# SKAARDUINO-POE_v1_0.net
KiCad netlist of a schematic drawn in EAGLE
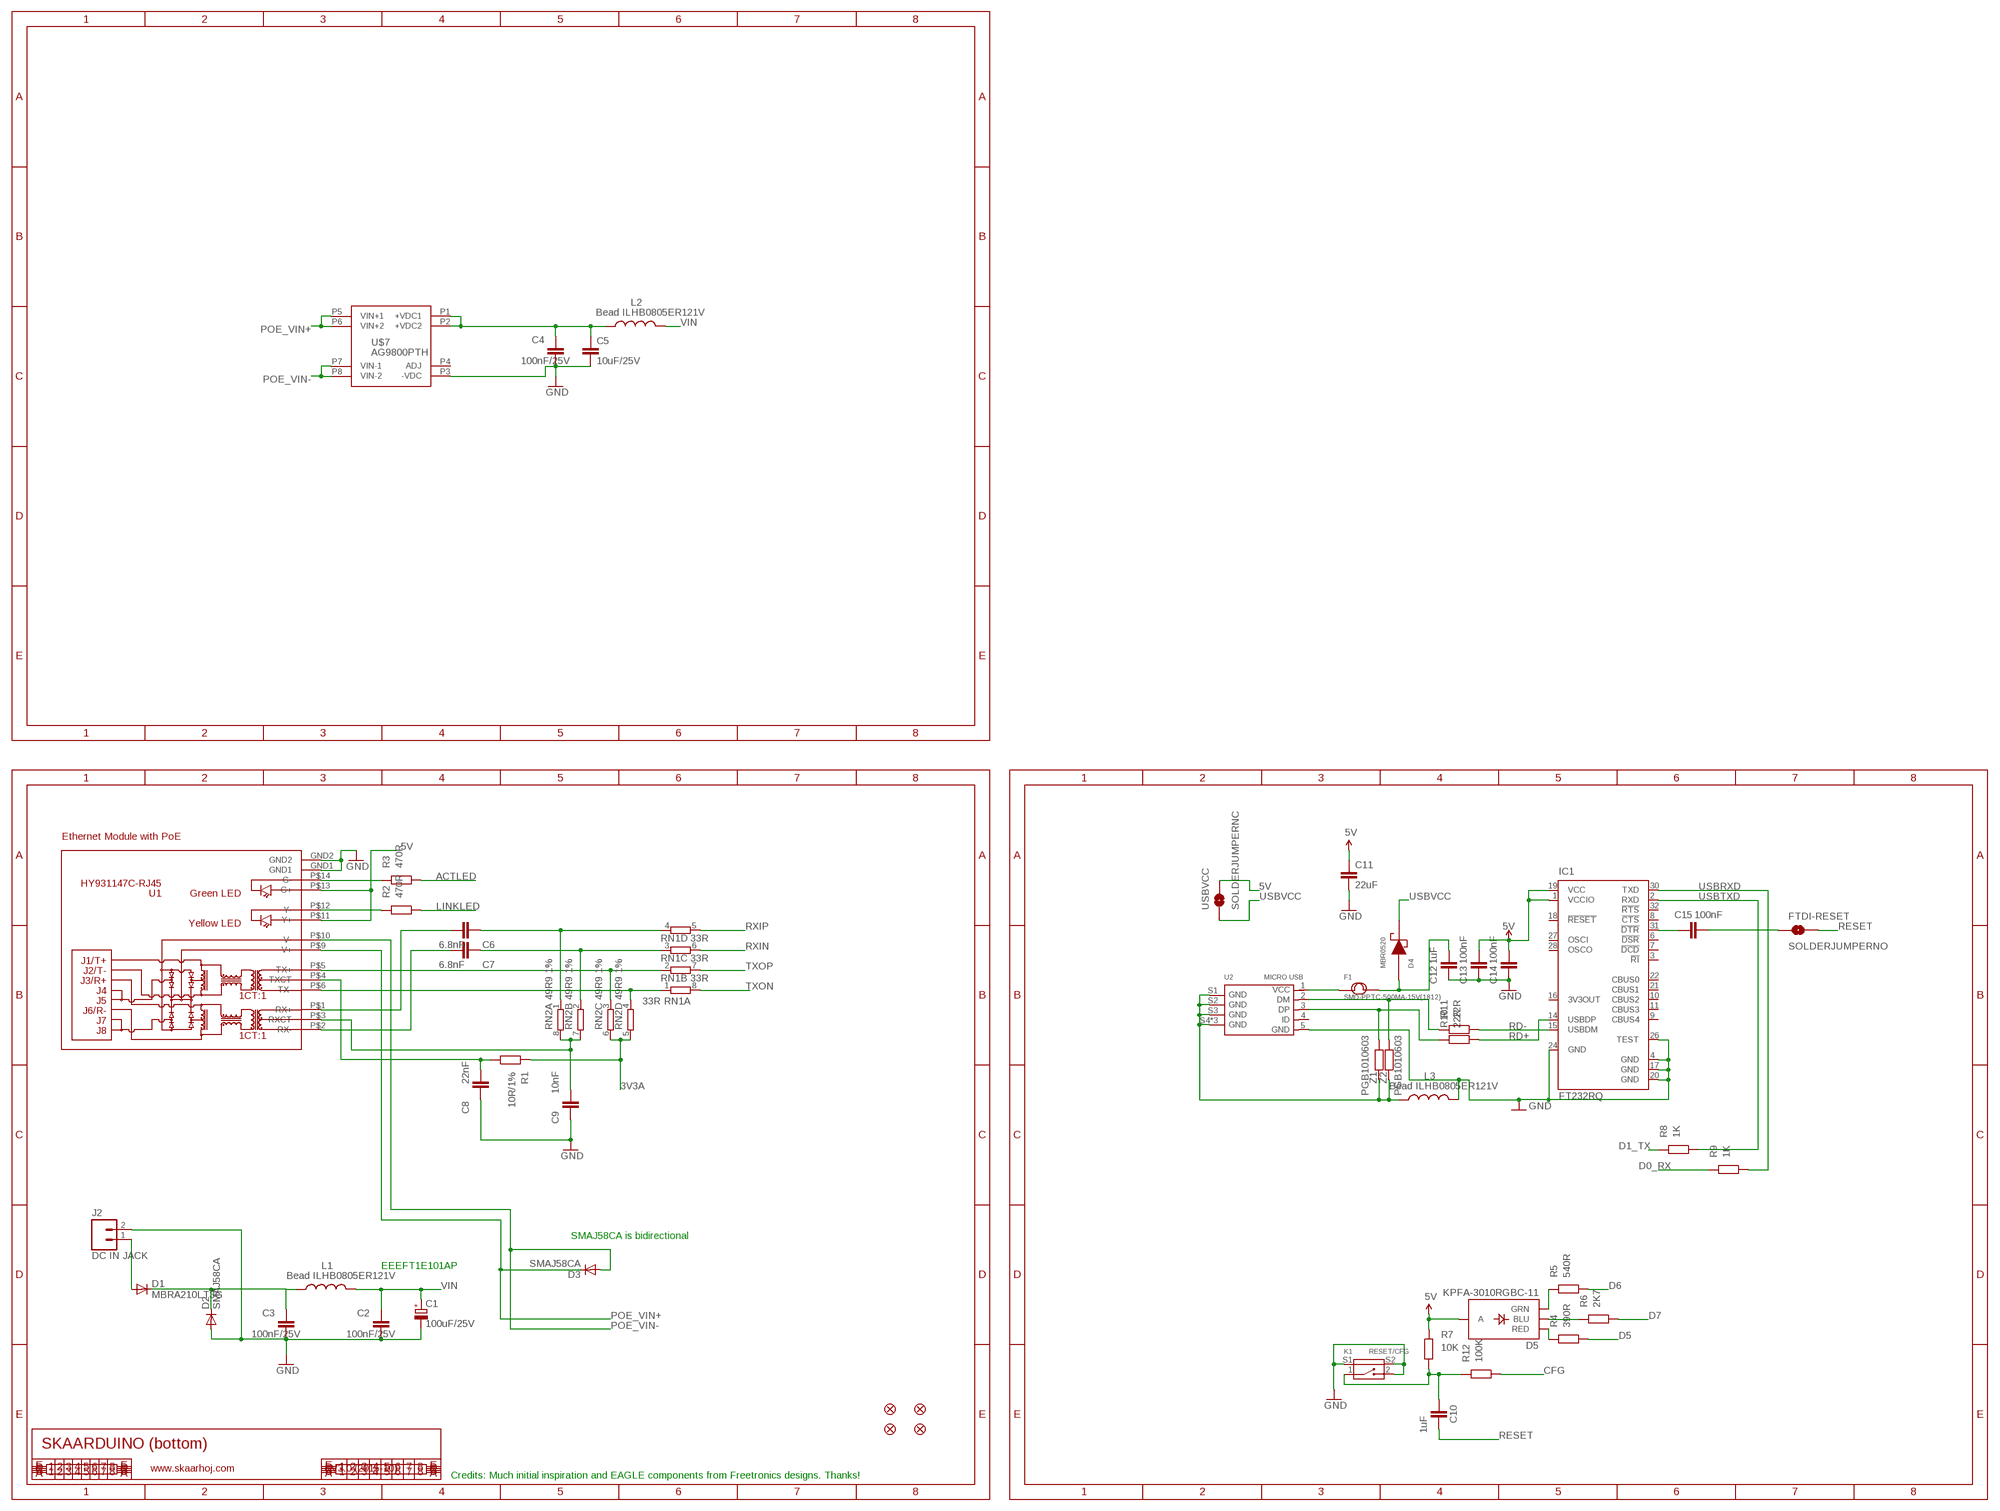
[diagram p0: schematic, sheet 1]
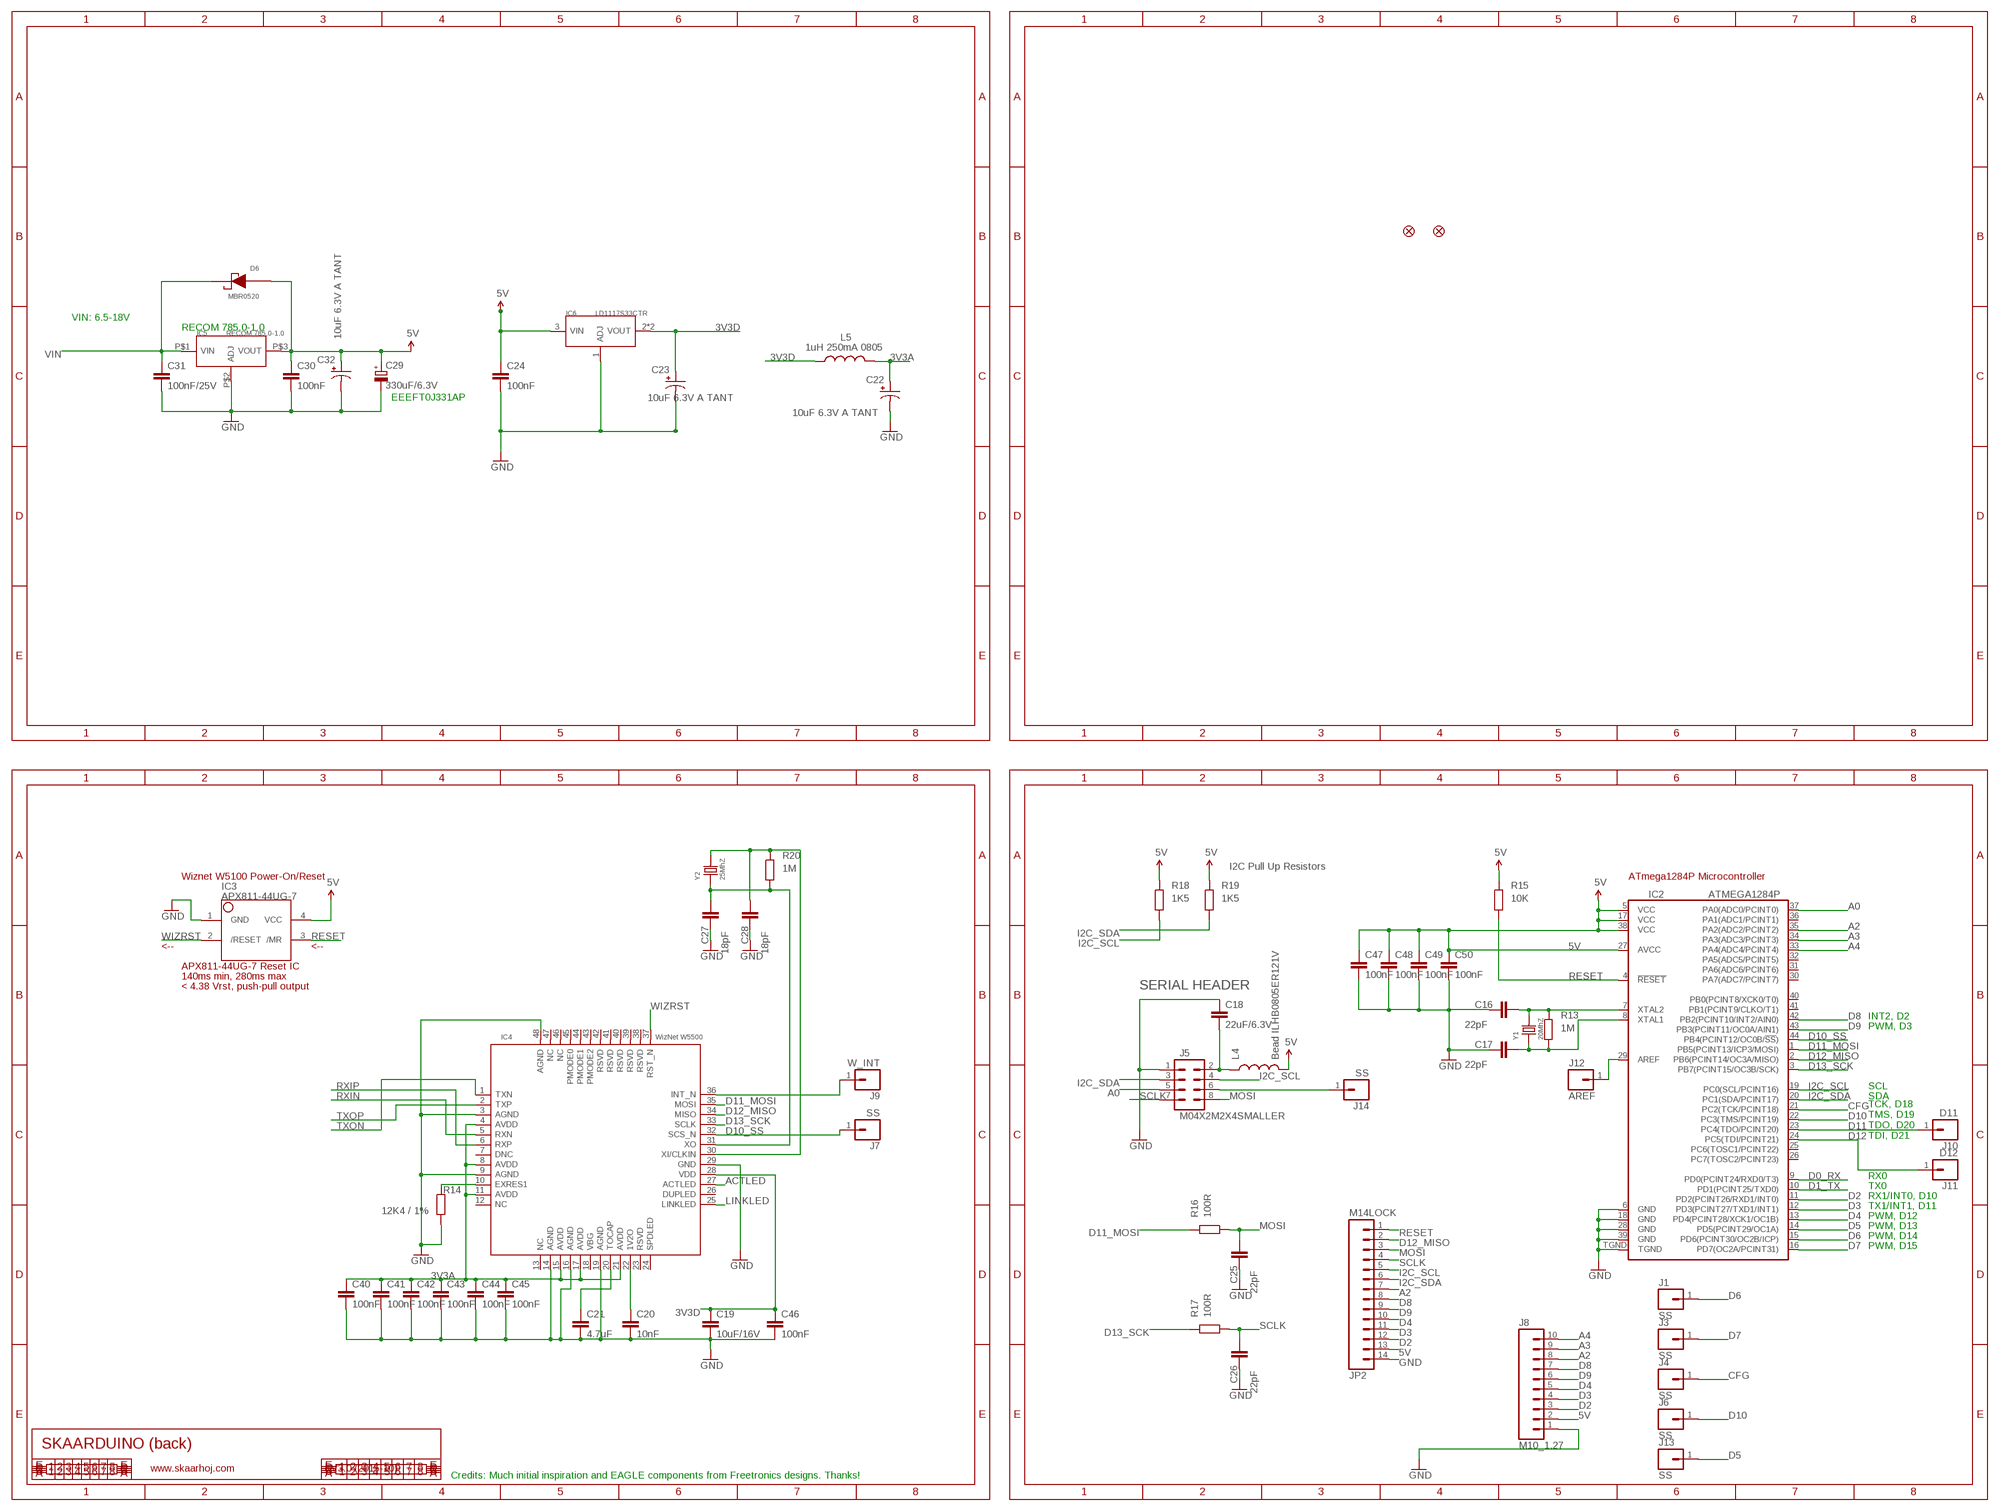
[diagram p1: schematic, sheet 2]

(export (version "E")
  (design (tool "Eeschema 10.0.6"))
  (components
    (comp (ref "C1")
      (value "100uF/25V")
      (footprint "eagle-import:PANASONIC_D")
      (libsource (lib "eagle-import") (part "CPOL-EUD"))
    )
    (comp (ref "C2")
      (value "100nF/25V")
      (footprint "eagle-import:C0402")
      (libsource (lib "eagle-import") (part "CAP0402"))
    )
    (comp (ref "C3")
      (value "100nF/25V")
      (footprint "eagle-import:C0402")
      (libsource (lib "eagle-import") (part "CAP0402"))
    )
    (comp (ref "C4")
      (value "100nF/25V")
      (footprint "eagle-import:C0402")
      (libsource (lib "eagle-import") (part "CAP0402"))
    )
    (comp (ref "C5")
      (value "10uF/25V")
      (footprint "eagle-import:0805")
      (libsource (lib "eagle-import") (part "CAP0805"))
    )
    (comp (ref "C6")
      (value "6.8nF")
      (footprint "eagle-import:0402C")
      (libsource (lib "eagle-import") (part "C-EU0402C"))
    )
    (comp (ref "C7")
      (value "6.8nF")
      (footprint "eagle-import:0402C")
      (libsource (lib "eagle-import") (part "C-EU0402C"))
    )
    (comp (ref "C8")
      (value "22nF")
      (footprint "eagle-import:0402C")
      (libsource (lib "eagle-import") (part "C-EU0402C"))
    )
    (comp (ref "C9")
      (value "10nF")
      (footprint "eagle-import:0402C")
      (libsource (lib "eagle-import") (part "C-EU0402C"))
    )
    (comp (ref "C10")
      (value "1uF")
      (footprint "eagle-import:0402C")
      (libsource (lib "eagle-import") (part "C-EU0402C"))
    )
    (comp (ref "C11")
      (value "22uF")
      (footprint "eagle-import:0805")
      (libsource (lib "eagle-import") (part "CAP0805"))
    )
    (comp (ref "C12")
      (value "1uF")
      (footprint "eagle-import:0402C")
      (libsource (lib "eagle-import") (part "C-EU0402C"))
    )
    (comp (ref "C13")
      (value "100nF")
      (footprint "eagle-import:0402C")
      (libsource (lib "eagle-import") (part "C-EU0402C"))
    )
    (comp (ref "C14")
      (value "100nF")
      (footprint "eagle-import:0402C")
      (libsource (lib "eagle-import") (part "C-EU0402C"))
    )
    (comp (ref "C15")
      (value "100nF")
      (footprint "eagle-import:0402C")
      (libsource (lib "eagle-import") (part "C-EU0402C"))
    )
    (comp (ref "D1")
      (value "MBRA210LT3G")
      (footprint "eagle-import:SMA-DIODE")
      (libsource (lib "eagle-import") (part "DIODESMA"))
    )
    (comp (ref "D2")
      (value "SMAJ58CA")
      (footprint "eagle-import:SMA-DIODE")
      (libsource (lib "eagle-import") (part "DIODESMA"))
    )
    (comp (ref "D3")
      (value "SMAJ58CA")
      (footprint "eagle-import:SMA-DIODE")
      (libsource (lib "eagle-import") (part "DIODESMA"))
    )
    (comp (ref "D4")
      (value "MBR0520")
      (footprint "eagle-import:SOD-123")
      (libsource (lib "eagle-import") (part "MBR0520"))
    )
    (comp (ref "D5")
      (value "KPFA-3010RGBC-11")
      (footprint "eagle-import:LED-TRICOLOR-SMD")
      (libsource (lib "eagle-import") (part "LED-TRICOLOR"))
    )
    (comp (ref "F1")
      (value "SMD-PPTC-500MA-15V(1812)")
      (footprint "eagle-import:F1812")
      (libsource (lib "eagle-import") (part "SMD-PPTC-500MA-15V(1812)"))
    )
    (comp (ref "FID1")
      (value "FIDUCIAL1X2.5")
      (footprint "eagle-import:FIDUCIAL-1X2.5")
      (libsource (lib "eagle-import") (part "FIDUCIAL1X2.5"))
    )
    (comp (ref "FID2")
      (value "FIDUCIAL1X2.5")
      (footprint "eagle-import:FIDUCIAL-1X2.5")
      (libsource (lib "eagle-import") (part "FIDUCIAL1X2.5"))
    )
    (comp (ref "FID3")
      (value "FIDUCIAL1X2.5")
      (footprint "eagle-import:FIDUCIAL-1X2.5")
      (libsource (lib "eagle-import") (part "FIDUCIAL1X2.5"))
    )
    (comp (ref "FID4")
      (value "FIDUCIAL1X2.5")
      (footprint "eagle-import:FIDUCIAL-1X2.5")
      (libsource (lib "eagle-import") (part "FIDUCIAL1X2.5"))
    )
    (comp (ref "FTDI-RESET")
      (value "SOLDERJUMPERNO")
      (footprint "eagle-import:SJ_2S-NO")
      (libsource (lib "eagle-import") (part "SOLDERJUMPERNO"))
    )
    (comp (ref "IC1")
      (value "FT232RQ")
      (footprint "eagle-import:QFN32")
      (libsource (lib "eagle-import") (part "FT232RQ"))
    )
    (comp (ref "J2")
      (value "DC IN JACK")
      (footprint "eagle-import:1X02")
      (libsource (lib "eagle-import") (part "M02PTH"))
    )
    (comp (ref "K1")
      (value "RESET/CFG")
      (footprint "eagle-import:SW4-SMD-7.0X3.5X3.5MM-90D")
      (fields (field (name "MPN") "TS-1188E"))
      (libsource (lib "eagle-import") (part "SMD-BUTTON-2+2P"))
    )
    (comp (ref "L1")
      (value "Bead ILHB0805ER121V")
      (footprint "eagle-import:L2012C")
      (libsource (lib "eagle-import") (part "L-USL2012C"))
    )
    (comp (ref "L2")
      (value "Bead ILHB0805ER121V")
      (footprint "eagle-import:L2012C")
      (libsource (lib "eagle-import") (part "L-USL2012C"))
    )
    (comp (ref "L3")
      (value "Bead ILHB0805ER121V")
      (footprint "eagle-import:L2012C")
      (libsource (lib "eagle-import") (part "L-USL2012C"))
    )
    (comp (ref "R1")
      (value "10R/1%")
      (footprint "eagle-import:0402")
      (libsource (lib "eagle-import") (part "freetronics-jon_RESISTOR0402"))
    )
    (comp (ref "R2")
      (value "470R")
      (footprint "eagle-import:0402")
      (libsource (lib "eagle-import") (part "freetronics-jon_RESISTOR0402"))
    )
    (comp (ref "R3")
      (value "470R")
      (footprint "eagle-import:0402")
      (libsource (lib "eagle-import") (part "freetronics-jon_RESISTOR0402"))
    )
    (comp (ref "R4")
      (value "390R")
      (footprint "eagle-import:0402")
      (libsource (lib "eagle-import") (part "freetronics-jon_RESISTOR0402"))
    )
    (comp (ref "R5")
      (value "540R")
      (footprint "eagle-import:0402")
      (libsource (lib "eagle-import") (part "freetronics-jon_RESISTOR0402"))
    )
    (comp (ref "R6")
      (value "2K7")
      (footprint "eagle-import:0402")
      (libsource (lib "eagle-import") (part "freetronics-jon_RESISTOR0402"))
    )
    (comp (ref "R7")
      (value "10K")
      (footprint "eagle-import:0402")
      (libsource (lib "eagle-import") (part "freetronics-jon_RESISTOR0402"))
    )
    (comp (ref "R8")
      (value "1K")
      (footprint "eagle-import:0402")
      (libsource (lib "eagle-import") (part "freetronics-jon_RESISTOR0402"))
    )
    (comp (ref "R9")
      (value "1K")
      (footprint "eagle-import:0402")
      (libsource (lib "eagle-import") (part "freetronics-jon_RESISTOR0402"))
    )
    (comp (ref "R10")
      (value "22R")
      (footprint "eagle-import:0402")
      (libsource (lib "eagle-import") (part "freetronics-jon_RESISTOR0402"))
    )
    (comp (ref "R11")
      (value "22R")
      (footprint "eagle-import:0402")
      (libsource (lib "eagle-import") (part "freetronics-jon_RESISTOR0402"))
    )
    (comp (ref "R12")
      (value "100K")
      (footprint "eagle-import:0402")
      (libsource (lib "eagle-import") (part "freetronics-jon_RESISTOR0402"))
    )
    (comp (ref "RN1")
      (value "33R")
      (footprint "eagle-import:CAY16")
      (libsource (lib "eagle-import") (part "4R-NCAY16"))
    )
    (comp (ref "RN2")
      (value "49R9 1%")
      (footprint "eagle-import:CAY16")
      (libsource (lib "eagle-import") (part "4R-NCAY16"))
    )
    (comp (ref "U$7")
      (value "AG9800PTH")
      (footprint "eagle-import:AG9800PTH")
      (libsource (lib "eagle-import") (part "AG9800PTH"))
    )
    (comp (ref "U1")
      (value "HY931147C-RJ45")
      (footprint "eagle-import:HY931147C")
      (libsource (lib "eagle-import") (part "HY931147C-RJ45"))
    )
    (comp (ref "U2")
      (value "MICRO USB")
      (footprint "eagle-import:MICRO-USB5+4P-SMD-0.65-B")
      (fields (field (name "MPN") "ST-USB-001G"))
      (libsource (lib "eagle-import") (part "MICRO-USB-SMD-B-WITHOUT-POST-W/P(ST-USB-001G)"))
    )
    (comp (ref "USBVCC")
      (value "SOLDERJUMPERNC")
      (footprint "eagle-import:SJ_2S")
      (libsource (lib "eagle-import") (part "SOLDERJUMPERNC"))
    )
    (comp (ref "Z1")
      (value "PGB1010603")
      (footprint "eagle-import:C0402")
      (libsource (lib "eagle-import") (part "RESISTOR0402"))
    )
    (comp (ref "Z2")
      (value "PGB1010603")
      (footprint "eagle-import:C0402")
      (libsource (lib "eagle-import") (part "RESISTOR0402"))
    )
    (comp (ref "C16")
      (value "22pF")
      (footprint "eagle-import:0402C")
      (libsource (lib "eagle-import") (part "C-EU0402C"))
    )
    (comp (ref "C17")
      (value "22pF")
      (footprint "eagle-import:0402C")
      (libsource (lib "eagle-import") (part "C-EU0402C"))
    )
    (comp (ref "C18")
      (value "22uF/6.3V")
      (footprint "eagle-import:0805")
      (libsource (lib "eagle-import") (part "CAP0805"))
    )
    (comp (ref "C19")
      (value "10uF/16V")
      (footprint "eagle-import:0805")
      (libsource (lib "eagle-import") (part "CAP0805"))
    )
    (comp (ref "C20")
      (value "10nF")
      (footprint "eagle-import:0402C")
      (libsource (lib "eagle-import") (part "C-EU0402C"))
    )
    (comp (ref "C21")
      (value "4.7uF")
      (footprint "eagle-import:0805")
      (libsource (lib "eagle-import") (part "CAP0805"))
    )
    (comp (ref "C22")
      (value "10uF 6.3V A TANT")
      (footprint "eagle-import:EIA3216")
      (libsource (lib "eagle-import") (part "CAP_POL1206"))
    )
    (comp (ref "C23")
      (value "10uF 6.3V A TANT")
      (footprint "eagle-import:EIA3216")
      (libsource (lib "eagle-import") (part "CAP_POL1206"))
    )
    (comp (ref "C24")
      (value "100nF")
      (footprint "eagle-import:0402C")
      (libsource (lib "eagle-import") (part "C-EU0402C"))
    )
    (comp (ref "C25")
      (value "22pF")
      (footprint "eagle-import:0402C")
      (libsource (lib "eagle-import") (part "C-EU0402C"))
    )
    (comp (ref "C26")
      (value "22pF")
      (footprint "eagle-import:0402C")
      (libsource (lib "eagle-import") (part "C-EU0402C"))
    )
    (comp (ref "C27")
      (value "18pF")
      (footprint "eagle-import:0402C")
      (libsource (lib "eagle-import") (part "C-EU0402C"))
    )
    (comp (ref "C28")
      (value "18pF")
      (footprint "eagle-import:0402C")
      (libsource (lib "eagle-import") (part "C-EU0402C"))
    )
    (comp (ref "C29")
      (value "330uF/6.3V")
      (footprint "eagle-import:PANASONIC_D")
      (libsource (lib "eagle-import") (part "CPOL-EUD"))
    )
    (comp (ref "C30")
      (value "100nF")
      (footprint "eagle-import:0402C")
      (libsource (lib "eagle-import") (part "C-EU0402C"))
    )
    (comp (ref "C31")
      (value "100nF/25V")
      (footprint "eagle-import:0402C")
      (libsource (lib "eagle-import") (part "C-EU0402C"))
    )
    (comp (ref "C32")
      (value "10uF 6.3V A TANT")
      (footprint "eagle-import:EIA3216")
      (libsource (lib "eagle-import") (part "CAP_POL1206"))
    )
    (comp (ref "C40")
      (value "100nF")
      (footprint "eagle-import:0402C")
      (libsource (lib "eagle-import") (part "C-EU0402C"))
    )
    (comp (ref "C41")
      (value "100nF")
      (footprint "eagle-import:0402C")
      (libsource (lib "eagle-import") (part "C-EU0402C"))
    )
    (comp (ref "C42")
      (value "100nF")
      (footprint "eagle-import:0402C")
      (libsource (lib "eagle-import") (part "C-EU0402C"))
    )
    (comp (ref "C43")
      (value "100nF")
      (footprint "eagle-import:0402C")
      (libsource (lib "eagle-import") (part "C-EU0402C"))
    )
    (comp (ref "C44")
      (value "100nF")
      (footprint "eagle-import:0402C")
      (libsource (lib "eagle-import") (part "C-EU0402C"))
    )
    (comp (ref "C45")
      (value "100nF")
      (footprint "eagle-import:0402C")
      (libsource (lib "eagle-import") (part "C-EU0402C"))
    )
    (comp (ref "C46")
      (value "100nF")
      (footprint "eagle-import:0402C")
      (libsource (lib "eagle-import") (part "C-EU0402C"))
    )
    (comp (ref "C47")
      (value "100nF")
      (footprint "eagle-import:0402C")
      (libsource (lib "eagle-import") (part "C-EU0402C"))
    )
    (comp (ref "C48")
      (value "100nF")
      (footprint "eagle-import:0402C")
      (libsource (lib "eagle-import") (part "C-EU0402C"))
    )
    (comp (ref "C49")
      (value "100nF")
      (footprint "eagle-import:0402C")
      (libsource (lib "eagle-import") (part "C-EU0402C"))
    )
    (comp (ref "C50")
      (value "100nF")
      (footprint "eagle-import:0402C")
      (libsource (lib "eagle-import") (part "C-EU0402C"))
    )
    (comp (ref "D6")
      (value "MBR0520")
      (footprint "eagle-import:SOD-123")
      (libsource (lib "eagle-import") (part "MBR0520"))
    )
    (comp (ref "FID5")
      (value "FIDUCIAL1X2.5")
      (footprint "eagle-import:FIDUCIAL-1X2.5")
      (libsource (lib "eagle-import") (part "FIDUCIAL1X2.5"))
    )
    (comp (ref "FID8")
      (value "FIDUCIAL1X2.5")
      (footprint "eagle-import:FIDUCIAL-1X2.5")
      (libsource (lib "eagle-import") (part "FIDUCIAL1X2.5"))
    )
    (comp (ref "IC2")
      (value "ATMEGA1284P")
      (footprint "eagle-import:QFN-44M1")
      (libsource (lib "eagle-import") (part "ATMEGA1284P"))
    )
    (comp (ref "IC3")
      (value "APX811-44UG-7")
      (footprint "eagle-import:SOT143-R")
      (libsource (lib "eagle-import") (part "APX81X-RESET-IC"))
    )
    (comp (ref "IC4")
      (value "WizNet W5500")
      (footprint "eagle-import:LQFP-48")
      (libsource (lib "eagle-import") (part "DRIVER-W5500"))
    )
    (comp (ref "IC5")
      (value "RECOM 785.0-1.0")
      (footprint "eagle-import:RECOM_785.0-1.0")
      (libsource (lib "eagle-import") (part "PMIC-LM317EMP"))
    )
    (comp (ref "IC6")
      (value "LD1117S33CTR")
      (footprint "eagle-import:SOT-223")
      (libsource (lib "eagle-import") (part "PMIC-LM317EMP-310030006"))
    )
    (comp (ref "J1")
      (value "SS")
      (footprint "eagle-import:M1X1")
      (libsource (lib "eagle-import") (part "M1X1TEST"))
    )
    (comp (ref "J3")
      (value "SS")
      (footprint "eagle-import:M1X1")
      (libsource (lib "eagle-import") (part "M1X1TEST"))
    )
    (comp (ref "J4")
      (value "SS")
      (footprint "eagle-import:M1X1")
      (libsource (lib "eagle-import") (part "M1X1TEST"))
    )
    (comp (ref "J5")
      (value "M04X2M2X4SMALLER")
      (footprint "eagle-import:M2X4SMALLER")
      (libsource (lib "eagle-import") (part "M04X2M2X4SMALLER"))
    )
    (comp (ref "J6")
      (value "SS")
      (footprint "eagle-import:M1X1")
      (libsource (lib "eagle-import") (part "M1X1TEST"))
    )
    (comp (ref "J7")
      (value "SS")
      (footprint "eagle-import:M1X1")
      (libsource (lib "eagle-import") (part "M1X1TEST"))
    )
    (comp (ref "J8")
      (value "M10_1.27")
      (footprint "eagle-import:M10X1")
      (libsource (lib "eagle-import") (part "M10_1.27"))
    )
    (comp (ref "J9")
      (value "W_INT")
      (footprint "eagle-import:M1X1")
      (libsource (lib "eagle-import") (part "M1X1TEST"))
    )
    (comp (ref "J10")
      (value "D11")
      (footprint "eagle-import:M1X1")
      (libsource (lib "eagle-import") (part "M1X1TEST"))
    )
    (comp (ref "J11")
      (value "D12")
      (footprint "eagle-import:M1X1")
      (libsource (lib "eagle-import") (part "M1X1TEST"))
    )
    (comp (ref "J12")
      (value "AREF")
      (footprint "eagle-import:M1X1")
      (libsource (lib "eagle-import") (part "M1X1TEST"))
    )
    (comp (ref "J13")
      (value "SS")
      (footprint "eagle-import:M1X1")
      (libsource (lib "eagle-import") (part "M1X1TEST"))
    )
    (comp (ref "J14")
      (value "SS")
      (footprint "eagle-import:M1X1")
      (libsource (lib "eagle-import") (part "M1X1TEST"))
    )
    (comp (ref "JP2")
      (value "M14LOCK")
      (footprint "eagle-import:1X14_LOCK")
      (libsource (lib "eagle-import") (part "M14LOCK"))
    )
    (comp (ref "L4")
      (value "Bead ILHB0805ER121V")
      (footprint "eagle-import:0805")
      (libsource (lib "eagle-import") (part "INDUCTOR0805"))
    )
    (comp (ref "L5")
      (value "1uH 250mA 0805")
      (footprint "eagle-import:L2012C")
      (libsource (lib "eagle-import") (part "L-USL2012C"))
    )
    (comp (ref "R13")
      (value "1M")
      (footprint "eagle-import:0402")
      (libsource (lib "eagle-import") (part "freetronics-jon_RESISTOR0402"))
    )
    (comp (ref "R14")
      (value "12K4 / 1%")
      (footprint "eagle-import:0402")
      (libsource (lib "eagle-import") (part "freetronics-jon_RESISTOR0402"))
    )
    (comp (ref "R15")
      (value "10K")
      (footprint "eagle-import:0402")
      (libsource (lib "eagle-import") (part "freetronics-jon_RESISTOR0402"))
    )
    (comp (ref "R16")
      (value "100R")
      (footprint "eagle-import:0402")
      (libsource (lib "eagle-import") (part "freetronics-jon_RESISTOR0402"))
    )
    (comp (ref "R17")
      (value "100R")
      (footprint "eagle-import:0402")
      (libsource (lib "eagle-import") (part "freetronics-jon_RESISTOR0402"))
    )
    (comp (ref "R18")
      (value "1K5")
      (footprint "eagle-import:0402")
      (libsource (lib "eagle-import") (part "freetronics-jon_RESISTOR0402"))
    )
    (comp (ref "R19")
      (value "1K5")
      (footprint "eagle-import:0402")
      (libsource (lib "eagle-import") (part "freetronics-jon_RESISTOR0402"))
    )
    (comp (ref "R20")
      (value "1M")
      (footprint "eagle-import:0402")
      (libsource (lib "eagle-import") (part "freetronics-jon_RESISTOR0402"))
    )
    (comp (ref "Y1")
      (value "20MhZ")
      (footprint "eagle-import:X2-SMD-5.0X3.2X1.3MM")
      (fields (field (name "MPN") "X053201602002"))
      (libsource (lib "eagle-import") (part "SMD-CRYSTAL-16MHZ-8PF-20PPM-40R(2P-5.0X3.2MM)"))
    )
    (comp (ref "Y2")
      (value "25MhZ")
      (footprint "eagle-import:X2-SMD-5.0X3.2X1.3MM")
      (fields (field (name "MPN") "X053201602002"))
      (libsource (lib "eagle-import") (part "SMD-CRYSTAL-16MHZ-8PF-20PPM-40R(2P-5.0X3.2MM)"))
    )
  )
  (nets
    (net (code "1") (name "3V3A") (class "Default")
      (node (ref "C22") (pin "A") (pinfunction "+_A") (pintype "passive"))
      (node (ref "C40") (pin "1") (pinfunction "1_1") (pintype "passive"))
      (node (ref "C41") (pin "1") (pinfunction "1_1") (pintype "passive"))
      (node (ref "C42") (pin "1") (pinfunction "1_1") (pintype "passive"))
      (node (ref "C43") (pin "1") (pinfunction "1_1") (pintype "passive"))
      (node (ref "C44") (pin "1") (pinfunction "1_1") (pintype "passive"))
      (node (ref "C45") (pin "1") (pinfunction "1_1") (pintype "passive"))
      (node (ref "IC4") (pin "11") (pinfunction "AVDD_11") (pintype "passive"))
      (node (ref "IC4") (pin "15") (pinfunction "AVDD_15") (pintype "passive"))
      (node (ref "IC4") (pin "17") (pinfunction "AVDD_17") (pintype "passive"))
      (node (ref "IC4") (pin "21") (pinfunction "AVDD_21") (pintype "passive"))
      (node (ref "IC4") (pin "4") (pinfunction "AVDD_4") (pintype "passive"))
      (node (ref "IC4") (pin "8") (pinfunction "AVDD_8") (pintype "passive"))
      (node (ref "L5") (pin "2") (pinfunction "2_2") (pintype "passive"))
      (node (ref "R1") (pin "2") (pinfunction "2_2") (pintype "passive"))
      (node (ref "RN2") (pin "5") (pinfunction "2_5") (pintype "passive"))
      (node (ref "RN2") (pin "6") (pinfunction "2_6") (pintype "passive"))
    )
    (net (code "2") (name "3V3D") (class "Default")
      (node (ref "C19") (pin "1") (pinfunction "1_1") (pintype "passive"))
      (node (ref "C23") (pin "A") (pinfunction "+_A") (pintype "passive"))
      (node (ref "C46") (pin "1") (pinfunction "1_1") (pintype "passive"))
      (node (ref "IC4") (pin "28") (pinfunction "VDD_28") (pintype "passive"))
      (node (ref "IC6") (pin "2") (pinfunction "VOUT_2") (pintype "bidirectional"))
      (node (ref "IC6") (pin "TER") (pinfunction "VOUT_TER") (pintype "bidirectional"))
      (node (ref "L5") (pin "1") (pinfunction "1_1") (pintype "passive"))
    )
    (net (code "3") (name "5V") (class "Default")
      (node (ref "C11") (pin "1") (pinfunction "1_1") (pintype "passive"))
      (node (ref "C13") (pin "2") (pinfunction "2_2") (pintype "passive"))
      (node (ref "C14") (pin "2") (pinfunction "2_2") (pintype "passive"))
      (node (ref "C24") (pin "1") (pinfunction "1_1") (pintype "passive"))
      (node (ref "C29") (pin "+") (pinfunction "+_+") (pintype "passive"))
      (node (ref "C30") (pin "1") (pinfunction "1_1") (pintype "passive"))
      (node (ref "C32") (pin "A") (pinfunction "+_A") (pintype "passive"))
      (node (ref "C47") (pin "1") (pinfunction "1_1") (pintype "passive"))
      (node (ref "C48") (pin "1") (pinfunction "1_1") (pintype "passive"))
      (node (ref "C49") (pin "1") (pinfunction "1_1") (pintype "passive"))
      (node (ref "C50") (pin "1") (pinfunction "1_1") (pintype "passive"))
      (node (ref "D5") (pin "A") (pinfunction "A_A") (pintype "bidirectional"))
      (node (ref "D6") (pin "2") (pinfunction "AN_2") (pintype "passive"))
      (node (ref "IC1") (pin "1") (pinfunction "VCCIO_1") (pintype "power_in"))
      (node (ref "IC1") (pin "19") (pinfunction "VCC_19") (pintype "power_in"))
      (node (ref "IC2") (pin "17") (pinfunction "VCC_17") (pintype "bidirectional"))
      (node (ref "IC2") (pin "27") (pinfunction "AVCC_27") (pintype "bidirectional"))
      (node (ref "IC2") (pin "38") (pinfunction "VCC_38") (pintype "bidirectional"))
      (node (ref "IC2") (pin "5") (pinfunction "VCC_5") (pintype "bidirectional"))
      (node (ref "IC3") (pin "4") (pinfunction "VCC_4") (pintype "power_in"))
      (node (ref "IC5") (pin "P$3") (pinfunction "VOUT_P$3") (pintype "bidirectional"))
      (node (ref "IC6") (pin "3") (pinfunction "VIN_3") (pintype "bidirectional"))
      (node (ref "J8") (pin "2") (pinfunction "2_2") (pintype "passive"))
      (node (ref "JP2") (pin "13") (pinfunction "13_13") (pintype "passive"))
      (node (ref "L4") (pin "2") (pinfunction "2_2") (pintype "passive"))
      (node (ref "R15") (pin "2") (pinfunction "2_2") (pintype "passive"))
      (node (ref "R18") (pin "2") (pinfunction "2_2") (pintype "passive"))
      (node (ref "R19") (pin "2") (pinfunction "2_2") (pintype "passive"))
      (node (ref "R7") (pin "2") (pinfunction "2_2") (pintype "passive"))
      (node (ref "U1") (pin "P$11") (pinfunction "Y+_P$11") (pintype "bidirectional"))
      (node (ref "U1") (pin "P$13") (pinfunction "G+_P$13") (pintype "bidirectional"))
      (node (ref "USBVCC") (pin "2") (pinfunction "2_2") (pintype "passive"))
    )
    (net (code "4") (name "A0") (class "Default")
      (node (ref "IC2") (pin "37") (pinfunction "PA0(ADC0/PCINT0)_37") (pintype "bidirectional"))
      (node (ref "J5") (pin "5") (pinfunction "5_5") (pintype "passive"))
    )
    (net (code "5") (name "A2") (class "Default")
      (node (ref "IC2") (pin "35") (pinfunction "PA2(ADC2/PCINT2)_35") (pintype "bidirectional"))
      (node (ref "J8") (pin "8") (pinfunction "8_8") (pintype "passive"))
      (node (ref "JP2") (pin "7") (pinfunction "7_7") (pintype "passive"))
    )
    (net (code "6") (name "A3") (class "Default")
      (node (ref "IC2") (pin "34") (pinfunction "PA3(ADC3/PCINT3)_34") (pintype "bidirectional"))
      (node (ref "J8") (pin "9") (pinfunction "9_9") (pintype "passive"))
    )
    (net (code "7") (name "A4") (class "Default")
      (node (ref "IC2") (pin "33") (pinfunction "PA4(ADC4/PCINT4)_33") (pintype "bidirectional"))
      (node (ref "J8") (pin "10") (pinfunction "10_10") (pintype "passive"))
    )
    (net (code "8") (name "ACTLED") (class "Default")
      (node (ref "IC4") (pin "27") (pinfunction "ACTLED_27") (pintype "passive"))
      (node (ref "R3") (pin "1") (pinfunction "1_1") (pintype "passive"))
    )
    (net (code "9") (name "CFG") (class "Default")
      (node (ref "IC2") (pin "21") (pinfunction "PC2(TCK/PCINT18)_21") (pintype "bidirectional"))
      (node (ref "J4") (pin "1") (pinfunction "5_1") (pintype "passive"))
      (node (ref "R12") (pin "1") (pinfunction "1_1") (pintype "passive"))
    )
    (net (code "10") (name "D0_RX") (class "Default")
      (node (ref "IC2") (pin "9") (pinfunction "PD0(PCINT24/RXD0/T3)_9") (pintype "bidirectional"))
      (node (ref "R9") (pin "2") (pinfunction "2_2") (pintype "passive"))
    )
    (net (code "11") (name "D1_TX") (class "Default")
      (node (ref "IC2") (pin "10") (pinfunction "PD1(PCINT25/TXD0)_10") (pintype "bidirectional"))
      (node (ref "R8") (pin "2") (pinfunction "2_2") (pintype "passive"))
    )
    (net (code "12") (name "D2") (class "Default")
      (node (ref "IC2") (pin "11") (pinfunction "PD2(PCINT26/RXD1/INT0)_11") (pintype "bidirectional"))
      (node (ref "J8") (pin "3") (pinfunction "3_3") (pintype "passive"))
      (node (ref "JP2") (pin "12") (pinfunction "12_12") (pintype "passive"))
    )
    (net (code "13") (name "D3") (class "Default")
      (node (ref "IC2") (pin "12") (pinfunction "PD3(PCINT27/TXD1/INT1)_12") (pintype "bidirectional"))
      (node (ref "J8") (pin "4") (pinfunction "4_4") (pintype "passive"))
      (node (ref "JP2") (pin "11") (pinfunction "11_11") (pintype "passive"))
    )
    (net (code "14") (name "D4") (class "Default")
      (node (ref "IC2") (pin "13") (pinfunction "PD4(PCINT28/XCK1/OC1B)_13") (pintype "bidirectional"))
      (node (ref "J8") (pin "5") (pinfunction "5_5") (pintype "passive"))
      (node (ref "JP2") (pin "10") (pinfunction "10_10") (pintype "passive"))
    )
    (net (code "15") (name "D5") (class "Default")
      (node (ref "IC2") (pin "14") (pinfunction "PD5(PCINT29/OC1A)_14") (pintype "bidirectional"))
      (node (ref "J13") (pin "1") (pinfunction "5_1") (pintype "passive"))
      (node (ref "R4") (pin "1") (pinfunction "1_1") (pintype "passive"))
    )
    (net (code "16") (name "D6") (class "Default")
      (node (ref "IC2") (pin "15") (pinfunction "PD6(PCINT30/OC2B/ICP)_15") (pintype "bidirectional"))
      (node (ref "J1") (pin "1") (pinfunction "5_1") (pintype "passive"))
      (node (ref "R5") (pin "1") (pinfunction "1_1") (pintype "passive"))
    )
    (net (code "17") (name "D7") (class "Default")
      (node (ref "IC2") (pin "16") (pinfunction "PD7(OC2A/PCINT31)_16") (pintype "bidirectional"))
      (node (ref "J3") (pin "1") (pinfunction "5_1") (pintype "passive"))
      (node (ref "R6") (pin "1") (pinfunction "1_1") (pintype "passive"))
    )
    (net (code "18") (name "D8") (class "Default")
      (node (ref "IC2") (pin "42") (pinfunction "PB2(PCINT10/INT2/AIN0)_42") (pintype "bidirectional"))
      (node (ref "J8") (pin "7") (pinfunction "7_7") (pintype "passive"))
      (node (ref "JP2") (pin "8") (pinfunction "8_8") (pintype "passive"))
    )
    (net (code "19") (name "D9") (class "Default")
      (node (ref "IC2") (pin "43") (pinfunction "PB3(PCINT11/OC0A/AIN1)_43") (pintype "bidirectional"))
      (node (ref "J8") (pin "6") (pinfunction "6_6") (pintype "passive"))
      (node (ref "JP2") (pin "9") (pinfunction "9_9") (pintype "passive"))
    )
    (net (code "20") (name "D10") (class "Default")
      (node (ref "IC2") (pin "22") (pinfunction "PC3(TMS/PCINT19)_22") (pintype "bidirectional"))
      (node (ref "J6") (pin "1") (pinfunction "5_1") (pintype "passive"))
    )
    (net (code "21") (name "D10_SS") (class "Default")
      (node (ref "IC2") (pin "44") (pinfunction "PB4(PCINT12/OC0B/~{SS})_44") (pintype "bidirectional"))
      (node (ref "IC4") (pin "32") (pinfunction "SCS_N_32") (pintype "passive"))
      (node (ref "J7") (pin "1") (pinfunction "5_1") (pintype "passive"))
    )
    (net (code "22") (name "D11") (class "Default")
      (node (ref "IC2") (pin "23") (pinfunction "PC4(TDO/PCINT20)_23") (pintype "bidirectional"))
      (node (ref "J10") (pin "1") (pinfunction "5_1") (pintype "passive"))
    )
    (net (code "23") (name "D11_MOSI") (class "Default")
      (node (ref "IC2") (pin "1") (pinfunction "PB5(PCINT13/ICP3/MOSI)_1") (pintype "bidirectional"))
      (node (ref "IC4") (pin "35") (pinfunction "MOSI_35") (pintype "passive"))
      (node (ref "R16") (pin "2") (pinfunction "2_2") (pintype "passive"))
    )
    (net (code "24") (name "D12") (class "Default")
      (node (ref "IC2") (pin "24") (pinfunction "PC5(TDI/PCINT21)_24") (pintype "bidirectional"))
      (node (ref "J11") (pin "1") (pinfunction "5_1") (pintype "passive"))
    )
    (net (code "25") (name "D12_MISO") (class "Default")
      (node (ref "IC2") (pin "2") (pinfunction "PB6(PCINT14/OC3A/MISO)_2") (pintype "bidirectional"))
      (node (ref "IC4") (pin "34") (pinfunction "MISO_34") (pintype "passive"))
      (node (ref "JP2") (pin "2") (pinfunction "2_2") (pintype "passive"))
    )
    (net (code "26") (name "D13_SCK") (class "Default")
      (node (ref "IC2") (pin "3") (pinfunction "PB7(PCINT15/OC3B/SCK)_3") (pintype "bidirectional"))
      (node (ref "IC4") (pin "33") (pinfunction "SCLK_33") (pintype "passive"))
      (node (ref "R17") (pin "2") (pinfunction "2_2") (pintype "passive"))
    )
    (net (code "27") (name "GND") (class "Default")
      (node (ref "C1") (pin "-") (pinfunction "-_-") (pintype "passive"))
      (node (ref "C11") (pin "2") (pinfunction "2_2") (pintype "passive"))
      (node (ref "C12") (pin "1") (pinfunction "1_1") (pintype "passive"))
      (node (ref "C13") (pin "1") (pinfunction "1_1") (pintype "passive"))
      (node (ref "C14") (pin "1") (pinfunction "1_1") (pintype "passive"))
      (node (ref "C16") (pin "1") (pinfunction "1_1") (pintype "passive"))
      (node (ref "C17") (pin "1") (pinfunction "1_1") (pintype "passive"))
      (node (ref "C18") (pin "1") (pinfunction "1_1") (pintype "passive"))
      (node (ref "C19") (pin "2") (pinfunction "2_2") (pintype "passive"))
      (node (ref "C2") (pin "2") (pinfunction "2_2") (pintype "passive"))
      (node (ref "C20") (pin "2") (pinfunction "2_2") (pintype "passive"))
      (node (ref "C21") (pin "2") (pinfunction "2_2") (pintype "passive"))
      (node (ref "C22") (pin "C") (pinfunction "-_C") (pintype "passive"))
      (node (ref "C23") (pin "C") (pinfunction "-_C") (pintype "passive"))
      (node (ref "C24") (pin "2") (pinfunction "2_2") (pintype "passive"))
      (node (ref "C25") (pin "1") (pinfunction "1_1") (pintype "passive"))
      (node (ref "C26") (pin "1") (pinfunction "1_1") (pintype "passive"))
      (node (ref "C27") (pin "1") (pinfunction "1_1") (pintype "passive"))
      (node (ref "C28") (pin "1") (pinfunction "1_1") (pintype "passive"))
      (node (ref "C29") (pin "-") (pinfunction "-_-") (pintype "passive"))
      (node (ref "C3") (pin "2") (pinfunction "2_2") (pintype "passive"))
      (node (ref "C30") (pin "2") (pinfunction "2_2") (pintype "passive"))
      (node (ref "C31") (pin "2") (pinfunction "2_2") (pintype "passive"))
      (node (ref "C32") (pin "C") (pinfunction "-_C") (pintype "passive"))
      (node (ref "C4") (pin "2") (pinfunction "2_2") (pintype "passive"))
      (node (ref "C40") (pin "2") (pinfunction "2_2") (pintype "passive"))
      (node (ref "C41") (pin "2") (pinfunction "2_2") (pintype "passive"))
      (node (ref "C42") (pin "2") (pinfunction "2_2") (pintype "passive"))
      (node (ref "C43") (pin "2") (pinfunction "2_2") (pintype "passive"))
      (node (ref "C44") (pin "2") (pinfunction "2_2") (pintype "passive"))
      (node (ref "C45") (pin "2") (pinfunction "2_2") (pintype "passive"))
      (node (ref "C46") (pin "2") (pinfunction "2_2") (pintype "passive"))
      (node (ref "C47") (pin "2") (pinfunction "2_2") (pintype "passive"))
      (node (ref "C48") (pin "2") (pinfunction "2_2") (pintype "passive"))
      (node (ref "C49") (pin "2") (pinfunction "2_2") (pintype "passive"))
      (node (ref "C5") (pin "2") (pinfunction "2_2") (pintype "passive"))
      (node (ref "C50") (pin "2") (pinfunction "2_2") (pintype "passive"))
      (node (ref "C8") (pin "1") (pinfunction "1_1") (pintype "passive"))
      (node (ref "C9") (pin "1") (pinfunction "1_1") (pintype "passive"))
      (node (ref "D2") (pin "A") (pinfunction "A_A") (pintype "passive"))
      (node (ref "IC1") (pin "17") (pinfunction "GND_17") (pintype "power_in"))
      (node (ref "IC1") (pin "20") (pinfunction "GND_20") (pintype "power_in"))
      (node (ref "IC1") (pin "24") (pinfunction "GND_24") (pintype "power_in"))
      (node (ref "IC1") (pin "26") (pinfunction "TEST_26") (pintype "input"))
      (node (ref "IC1") (pin "4") (pinfunction "GND_4") (pintype "power_in"))
      (node (ref "IC2") (pin "18") (pinfunction "GND_18") (pintype "bidirectional"))
      (node (ref "IC2") (pin "28") (pinfunction "GND_28") (pintype "bidirectional"))
      (node (ref "IC2") (pin "39") (pinfunction "GND_39") (pintype "bidirectional"))
      (node (ref "IC2") (pin "6") (pinfunction "GND_6") (pintype "bidirectional"))
      (node (ref "IC2") (pin "TGND") (pinfunction "TGND_TGND") (pintype "bidirectional"))
      (node (ref "IC3") (pin "1") (pinfunction "GND_1") (pintype "power_in"))
      (node (ref "IC4") (pin "14") (pinfunction "AGND_14") (pintype "passive"))
      (node (ref "IC4") (pin "16") (pinfunction "AGND_16") (pintype "passive"))
      (node (ref "IC4") (pin "19") (pinfunction "AGND_19") (pintype "passive"))
      (node (ref "IC4") (pin "29") (pinfunction "GND_29") (pintype "passive"))
      (node (ref "IC4") (pin "3") (pinfunction "AGND_3") (pintype "passive"))
      (node (ref "IC4") (pin "48") (pinfunction "AGND_48") (pintype "passive"))
      (node (ref "IC4") (pin "9") (pinfunction "AGND_9") (pintype "passive"))
      (node (ref "IC5") (pin "P$2") (pinfunction "ADJ_P$2") (pintype "bidirectional"))
      (node (ref "IC6") (pin "1") (pinfunction "ADJ_1") (pintype "bidirectional"))
      (node (ref "J2") (pin "2") (pinfunction "2_2") (pintype "passive"))
      (node (ref "J5") (pin "1") (pinfunction "1_1") (pintype "passive"))
      (node (ref "J8") (pin "1") (pinfunction "1_1") (pintype "passive"))
      (node (ref "JP2") (pin "14") (pinfunction "14_14") (pintype "passive"))
      (node (ref "K1") (pin "2") (pinfunction "2_2") (pintype "bidirectional"))
      (node (ref "K1") (pin "S1") (pinfunction "S1_S1") (pintype "bidirectional"))
      (node (ref "K1") (pin "S2") (pinfunction "S2_S2") (pintype "bidirectional"))
      (node (ref "L3") (pin "2") (pinfunction "2_2") (pintype "passive"))
      (node (ref "R14") (pin "1") (pinfunction "1_1") (pintype "passive"))
      (node (ref "U$7") (pin "P3") (pinfunction "-VDC_P3") (pintype "bidirectional"))
      (node (ref "U1") (pin "GND1") (pinfunction "GND1_GND1") (pintype "bidirectional"))
      (node (ref "U1") (pin "GND2") (pinfunction "GND2_GND2") (pintype "bidirectional"))
      (node (ref "U2") (pin "5") (pinfunction "GND_5") (pintype "bidirectional"))
    )
    (net (code "28") (name "I2C_SCL") (class "Default")
      (node (ref "IC2") (pin "19") (pinfunction "PC0(SCL/PCINT16)_19") (pintype "bidirectional"))
      (node (ref "J5") (pin "4") (pinfunction "4_4") (pintype "passive"))
      (node (ref "JP2") (pin "5") (pinfunction "5_5") (pintype "passive"))
      (node (ref "R18") (pin "1") (pinfunction "1_1") (pintype "passive"))
    )
    (net (code "29") (name "I2C_SDA") (class "Default")
      (node (ref "IC2") (pin "20") (pinfunction "PC1(SDA/PCINT17)_20") (pintype "bidirectional"))
      (node (ref "J5") (pin "3") (pinfunction "3_3") (pintype "passive"))
      (node (ref "JP2") (pin "6") (pinfunction "6_6") (pintype "passive"))
      (node (ref "R19") (pin "1") (pinfunction "1_1") (pintype "passive"))
    )
    (net (code "30") (name "LINKLED") (class "Default")
      (node (ref "IC4") (pin "25") (pinfunction "LINKLED_25") (pintype "passive"))
      (node (ref "R2") (pin "1") (pinfunction "1_1") (pintype "passive"))
    )
    (net (code "31") (name "MOSI") (class "Default")
      (node (ref "C25") (pin "2") (pinfunction "2_2") (pintype "passive"))
      (node (ref "J5") (pin "8") (pinfunction "8_8") (pintype "passive"))
      (node (ref "JP2") (pin "3") (pinfunction "3_3") (pintype "passive"))
      (node (ref "R16") (pin "1") (pinfunction "1_1") (pintype "passive"))
    )
    (net (code "32") (name "Net-(C3-Pad1)") (class "Default")
      (node (ref "C3") (pin "1") (pinfunction "1_1") (pintype "passive"))
      (node (ref "D1") (pin "C") (pinfunction "C_C") (pintype "passive"))
      (node (ref "D2") (pin "C") (pinfunction "C_C") (pintype "passive"))
      (node (ref "L1") (pin "1") (pinfunction "1_1") (pintype "passive"))
    )
    (net (code "33") (name "Net-(C10-Pad2)") (class "Default")
      (node (ref "C10") (pin "2") (pinfunction "2_2") (pintype "passive"))
      (node (ref "K1") (pin "1") (pinfunction "1_1") (pintype "bidirectional"))
      (node (ref "R12") (pin "2") (pinfunction "2_2") (pintype "passive"))
      (node (ref "R7") (pin "1") (pinfunction "1_1") (pintype "passive"))
    )
    (net (code "34") (name "Net-(C15-Pad2)") (class "Default")
      (node (ref "C15") (pin "2") (pinfunction "2_2") (pintype "passive"))
      (node (ref "FTDI-RESET") (pin "1") (pinfunction "1_1") (pintype "passive"))
    )
    (net (code "35") (name "Net-(C18-Pad2)") (class "Default")
      (node (ref "C18") (pin "2") (pinfunction "2_2") (pintype "passive"))
      (node (ref "J5") (pin "2") (pinfunction "2_2") (pintype "passive"))
      (node (ref "L4") (pin "1") (pinfunction "1_1") (pintype "passive"))
    )
    (net (code "36") (name "Net-(D1-PadA)") (class "Default")
      (node (ref "D1") (pin "A") (pinfunction "A_A") (pintype "passive"))
      (node (ref "J2") (pin "1") (pinfunction "1_1") (pintype "passive"))
    )
    (net (code "37") (name "Net-(D4-AN)") (class "Default")
      (node (ref "C12") (pin "2") (pinfunction "2_2") (pintype "passive"))
      (node (ref "D4") (pin "2") (pinfunction "AN_2") (pintype "passive"))
      (node (ref "F1") (pin "2") (pinfunction "2_2") (pintype "bidirectional"))
    )
    (net (code "38") (name "Net-(D5-BLU)") (class "Default")
      (node (ref "D5") (pin "B") (pinfunction "BLU_B") (pintype "bidirectional"))
      (node (ref "R6") (pin "2") (pinfunction "2_2") (pintype "passive"))
    )
    (net (code "39") (name "Net-(D5-GRN)") (class "Default")
      (node (ref "D5") (pin "G") (pinfunction "GRN_G") (pintype "bidirectional"))
      (node (ref "R5") (pin "2") (pinfunction "2_2") (pintype "passive"))
    )
    (net (code "40") (name "Net-(D5-RED)") (class "Default")
      (node (ref "D5") (pin "R") (pinfunction "RED_R") (pintype "bidirectional"))
      (node (ref "R4") (pin "2") (pinfunction "2_2") (pintype "passive"))
    )
    (net (code "41") (name "Net-(IC1-~{DTR})") (class "Default")
      (node (ref "C15") (pin "1") (pinfunction "1_1") (pintype "passive"))
      (node (ref "IC1") (pin "31") (pinfunction "~{DTR}_31") (pintype "output"))
    )
    (net (code "42") (name "Net-(IC2-AREF)") (class "Default")
      (node (ref "IC2") (pin "29") (pinfunction "AREF_29") (pintype "bidirectional"))
      (node (ref "J12") (pin "1") (pinfunction "5_1") (pintype "passive"))
    )
    (net (code "43") (name "Net-(IC2-XTAL1)") (class "Default")
      (node (ref "C17") (pin "2") (pinfunction "2_2") (pintype "passive"))
      (node (ref "IC2") (pin "8") (pinfunction "XTAL1_8") (pintype "bidirectional"))
      (node (ref "R13") (pin "1") (pinfunction "1_1") (pintype "passive"))
      (node (ref "Y1") (pin "1") (pinfunction "1_1") (pintype "passive"))
    )
    (net (code "44") (name "Net-(IC2-XTAL2)") (class "Default")
      (node (ref "C16") (pin "2") (pinfunction "2_2") (pintype "passive"))
      (node (ref "IC2") (pin "7") (pinfunction "XTAL2_7") (pintype "bidirectional"))
      (node (ref "R13") (pin "2") (pinfunction "2_2") (pintype "passive"))
      (node (ref "Y1") (pin "2") (pinfunction "2_2") (pintype "passive"))
    )
    (net (code "45") (name "Net-(IC4-1V2O)") (class "Default")
      (node (ref "C20") (pin "1") (pinfunction "1_1") (pintype "passive"))
      (node (ref "IC4") (pin "22") (pinfunction "1V2O_22") (pintype "passive"))
    )
    (net (code "46") (name "Net-(IC4-EXRES1)") (class "Default")
      (node (ref "IC4") (pin "10") (pinfunction "EXRES1_10") (pintype "passive"))
      (node (ref "R14") (pin "2") (pinfunction "2_2") (pintype "passive"))
    )
    (net (code "47") (name "Net-(IC4-INT_N)") (class "Default")
      (node (ref "IC4") (pin "36") (pinfunction "INT_N_36") (pintype "passive"))
      (node (ref "J9") (pin "1") (pinfunction "5_1") (pintype "passive"))
    )
    (net (code "48") (name "Net-(IC4-TOCAP)") (class "Default")
      (node (ref "C21") (pin "1") (pinfunction "1_1") (pintype "passive"))
      (node (ref "IC4") (pin "20") (pinfunction "TOCAP_20") (pintype "passive"))
    )
    (net (code "49") (name "Net-(IC4-XI{slash}CLKIN)") (class "Default")
      (node (ref "C28") (pin "2") (pinfunction "2_2") (pintype "passive"))
      (node (ref "IC4") (pin "30") (pinfunction "XI/CLKIN_30") (pintype "passive"))
      (node (ref "R20") (pin "2") (pinfunction "2_2") (pintype "passive"))
      (node (ref "Y2") (pin "2") (pinfunction "2_2") (pintype "passive"))
    )
    (net (code "50") (name "Net-(IC4-XO)") (class "Default")
      (node (ref "C27") (pin "2") (pinfunction "2_2") (pintype "passive"))
      (node (ref "IC4") (pin "31") (pinfunction "XO_31") (pintype "passive"))
      (node (ref "R20") (pin "1") (pinfunction "1_1") (pintype "passive"))
      (node (ref "Y2") (pin "1") (pinfunction "1_1") (pintype "passive"))
    )
    (net (code "51") (name "Net-(J14-5)") (class "Default")
      (node (ref "J14") (pin "1") (pinfunction "5_1") (pintype "passive"))
      (node (ref "J5") (pin "6") (pinfunction "6_6") (pintype "passive"))
    )
    (net (code "52") (name "Net-(L3-Pad1)") (class "Default")
      (node (ref "L3") (pin "1") (pinfunction "1_1") (pintype "passive"))
      (node (ref "U2") (pin "S1") (pinfunction "GND_S1") (pintype "bidirectional"))
      (node (ref "U2") (pin "S2") (pinfunction "GND_S2") (pintype "bidirectional"))
      (node (ref "U2") (pin "S3") (pinfunction "GND_S3") (pintype "bidirectional"))
      (node (ref "U2") (pin "S4") (pinfunction "GND_S4") (pintype "bidirectional"))
      (node (ref "U2") (pin "S5") (pinfunction "GND_S5") (pintype "bidirectional"))
      (node (ref "U2") (pin "S6") (pinfunction "GND_S6") (pintype "bidirectional"))
      (node (ref "Z1") (pin "2") (pinfunction "2_2") (pintype "passive"))
      (node (ref "Z2") (pin "2") (pinfunction "2_2") (pintype "passive"))
    )
    (net (code "53") (name "Net-(RN1B-1)") (class "Default")
      (node (ref "RN1") (pin "2") (pinfunction "1_2") (pintype "passive"))
      (node (ref "RN2") (pin "3") (pinfunction "1_3") (pintype "passive"))
      (node (ref "U1") (pin "P$5") (pinfunction "TX+_P$5") (pintype "bidirectional"))
    )
    (net (code "54") (name "Net-(RN1C-1)") (class "Default")
      (node (ref "C7") (pin "1") (pinfunction "1_1") (pintype "passive"))
      (node (ref "RN1") (pin "3") (pinfunction "1_3") (pintype "passive"))
      (node (ref "RN2") (pin "2") (pinfunction "1_2") (pintype "passive"))
    )
    (net (code "55") (name "Net-(RN1D-1)") (class "Default")
      (node (ref "C6") (pin "1") (pinfunction "1_1") (pintype "passive"))
      (node (ref "RN1") (pin "4") (pinfunction "1_4") (pintype "passive"))
      (node (ref "RN2") (pin "1") (pinfunction "1_1") (pintype "passive"))
    )
    (net (code "56") (name "Net-(RN2A-2)") (class "Default")
      (node (ref "C9") (pin "2") (pinfunction "2_2") (pintype "passive"))
      (node (ref "RN2") (pin "7") (pinfunction "2_7") (pintype "passive"))
      (node (ref "RN2") (pin "8") (pinfunction "2_8") (pintype "passive"))
      (node (ref "U1") (pin "P$3") (pinfunction "RXCT_P$3") (pintype "bidirectional"))
    )
    (net (code "57") (name "Net-(RN2D-1)") (class "Default")
      (node (ref "RN1") (pin "1") (pinfunction "1_1") (pintype "passive"))
      (node (ref "RN2") (pin "4") (pinfunction "1_4") (pintype "passive"))
      (node (ref "U1") (pin "P$6") (pinfunction "TX-_P$6") (pintype "bidirectional"))
    )
    (net (code "58") (name "Net-(U$7-+VDC1)") (class "Default")
      (node (ref "C4") (pin "1") (pinfunction "1_1") (pintype "passive"))
      (node (ref "C5") (pin "1") (pinfunction "1_1") (pintype "passive"))
      (node (ref "L2") (pin "1") (pinfunction "1_1") (pintype "passive"))
      (node (ref "U$7") (pin "P1") (pinfunction "+VDC1_P1") (pintype "bidirectional"))
      (node (ref "U$7") (pin "P2") (pinfunction "+VDC2_P2") (pintype "bidirectional"))
    )
    (net (code "59") (name "Net-(U1-G-)") (class "Default")
      (node (ref "R3") (pin "2") (pinfunction "2_2") (pintype "passive"))
      (node (ref "U1") (pin "P$14") (pinfunction "G-_P$14") (pintype "bidirectional"))
    )
    (net (code "60") (name "Net-(U1-RX+)") (class "Default")
      (node (ref "C6") (pin "2") (pinfunction "2_2") (pintype "passive"))
      (node (ref "U1") (pin "P$1") (pinfunction "RX+_P$1") (pintype "bidirectional"))
    )
    (net (code "61") (name "Net-(U1-RX-)") (class "Default")
      (node (ref "C7") (pin "2") (pinfunction "2_2") (pintype "passive"))
      (node (ref "U1") (pin "P$2") (pinfunction "RX-_P$2") (pintype "bidirectional"))
    )
    (net (code "62") (name "Net-(U1-TXCT)") (class "Default")
      (node (ref "C8") (pin "2") (pinfunction "2_2") (pintype "passive"))
      (node (ref "R1") (pin "1") (pinfunction "1_1") (pintype "passive"))
      (node (ref "U1") (pin "P$4") (pinfunction "TXCT_P$4") (pintype "bidirectional"))
    )
    (net (code "63") (name "Net-(U1-Y-)") (class "Default")
      (node (ref "R2") (pin "2") (pinfunction "2_2") (pintype "passive"))
      (node (ref "U1") (pin "P$12") (pinfunction "Y-_P$12") (pintype "bidirectional"))
    )
    (net (code "64") (name "Net-(U2-DM)") (class "Default")
      (node (ref "R11") (pin "2") (pinfunction "2_2") (pintype "passive"))
      (node (ref "U2") (pin "2") (pinfunction "DM_2") (pintype "bidirectional"))
      (node (ref "Z2") (pin "1") (pinfunction "1_1") (pintype "passive"))
    )
    (net (code "65") (name "Net-(U2-DP)") (class "Default")
      (node (ref "R10") (pin "2") (pinfunction "2_2") (pintype "passive"))
      (node (ref "U2") (pin "3") (pinfunction "DP_3") (pintype "bidirectional"))
      (node (ref "Z1") (pin "1") (pinfunction "1_1") (pintype "passive"))
    )
    (net (code "66") (name "Net-(U2-VCC)") (class "Default")
      (node (ref "F1") (pin "1") (pinfunction "1_1") (pintype "bidirectional"))
      (node (ref "U2") (pin "1") (pinfunction "VCC_1") (pintype "bidirectional"))
    )
    (net (code "67") (name "POE_VIN+") (class "Default")
      (node (ref "D3") (pin "C") (pinfunction "C_C") (pintype "passive"))
      (node (ref "U$7") (pin "P5") (pinfunction "VIN+1_P5") (pintype "power_in"))
      (node (ref "U$7") (pin "P6") (pinfunction "VIN+2_P6") (pintype "power_in"))
      (node (ref "U1") (pin "P$9") (pinfunction "V+_P$9") (pintype "bidirectional"))
    )
    (net (code "68") (name "POE_VIN-") (class "Default")
      (node (ref "D3") (pin "A") (pinfunction "A_A") (pintype "passive"))
      (node (ref "U$7") (pin "P7") (pinfunction "VIN-1_P7") (pintype "power_in"))
      (node (ref "U$7") (pin "P8") (pinfunction "VIN-2_P8") (pintype "power_in"))
      (node (ref "U1") (pin "P$10") (pinfunction "V-_P$10") (pintype "bidirectional"))
    )
    (net (code "69") (name "RD+") (class "Default")
      (node (ref "IC1") (pin "14") (pinfunction "USBDP_14") (pintype "bidirectional"))
      (node (ref "R10") (pin "1") (pinfunction "1_1") (pintype "passive"))
    )
    (net (code "70") (name "RD-") (class "Default")
      (node (ref "IC1") (pin "15") (pinfunction "USBDM_15") (pintype "bidirectional"))
      (node (ref "R11") (pin "1") (pinfunction "1_1") (pintype "passive"))
    )
    (net (code "71") (name "RESET") (class "Default")
      (node (ref "C10") (pin "1") (pinfunction "1_1") (pintype "passive"))
      (node (ref "FTDI-RESET") (pin "2") (pinfunction "2_2") (pintype "passive"))
      (node (ref "IC2") (pin "4") (pinfunction "~{RESET}_4") (pintype "bidirectional"))
      (node (ref "IC3") (pin "3") (pinfunction "/MR_3") (pintype "input"))
      (node (ref "JP2") (pin "1") (pinfunction "1_1") (pintype "passive"))
      (node (ref "R15") (pin "1") (pinfunction "1_1") (pintype "passive"))
    )
    (net (code "72") (name "RXIN") (class "Default")
      (node (ref "IC4") (pin "5") (pinfunction "RXN_5") (pintype "passive"))
      (node (ref "RN1") (pin "6") (pinfunction "2_6") (pintype "passive"))
    )
    (net (code "73") (name "RXIP") (class "Default")
      (node (ref "IC4") (pin "6") (pinfunction "RXP_6") (pintype "passive"))
      (node (ref "RN1") (pin "5") (pinfunction "2_5") (pintype "passive"))
    )
    (net (code "74") (name "SCLK") (class "Default")
      (node (ref "C26") (pin "2") (pinfunction "2_2") (pintype "passive"))
      (node (ref "J5") (pin "7") (pinfunction "7_7") (pintype "passive"))
      (node (ref "JP2") (pin "4") (pinfunction "4_4") (pintype "passive"))
      (node (ref "R17") (pin "1") (pinfunction "1_1") (pintype "passive"))
    )
    (net (code "75") (name "TXON") (class "Default")
      (node (ref "IC4") (pin "1") (pinfunction "TXN_1") (pintype "passive"))
      (node (ref "RN1") (pin "8") (pinfunction "2_8") (pintype "passive"))
    )
    (net (code "76") (name "TXOP") (class "Default")
      (node (ref "IC4") (pin "2") (pinfunction "TXP_2") (pintype "passive"))
      (node (ref "RN1") (pin "7") (pinfunction "2_7") (pintype "passive"))
    )
    (net (code "77") (name "USBRXD") (class "Default")
      (node (ref "IC1") (pin "30") (pinfunction "TXD_30") (pintype "output"))
      (node (ref "R9") (pin "1") (pinfunction "1_1") (pintype "passive"))
    )
    (net (code "78") (name "USBTXD") (class "Default")
      (node (ref "IC1") (pin "2") (pinfunction "RXD_2") (pintype "input"))
      (node (ref "R8") (pin "1") (pinfunction "1_1") (pintype "passive"))
    )
    (net (code "79") (name "USBVCC") (class "Default")
      (node (ref "D4") (pin "1") (pinfunction "CA_1") (pintype "passive"))
      (node (ref "USBVCC") (pin "1") (pinfunction "1_1") (pintype "passive"))
    )
    (net (code "80") (name "VIN") (class "Default")
      (node (ref "C1") (pin "+") (pinfunction "+_+") (pintype "passive"))
      (node (ref "C2") (pin "1") (pinfunction "1_1") (pintype "passive"))
      (node (ref "C31") (pin "1") (pinfunction "1_1") (pintype "passive"))
      (node (ref "D6") (pin "1") (pinfunction "CA_1") (pintype "passive"))
      (node (ref "IC5") (pin "P$1") (pinfunction "VIN_P$1") (pintype "bidirectional"))
      (node (ref "L1") (pin "2") (pinfunction "2_2") (pintype "passive"))
      (node (ref "L2") (pin "2") (pinfunction "2_2") (pintype "passive"))
    )
    (net (code "81") (name "WIZRST") (class "Default")
      (node (ref "IC3") (pin "2") (pinfunction "/RESET_2") (pintype "output"))
      (node (ref "IC4") (pin "37") (pinfunction "RST_N_37") (pintype "passive"))
    )
    (net (code "82") (name "unconnected-(IC1-3V3OUT-Pad16)") (class "Default")
      (node (ref "IC1") (pin "16") (pinfunction "3V3OUT_16") (pintype "output"))
    )
    (net (code "83") (name "unconnected-(IC1-CBUS0-Pad22)") (class "Default")
      (node (ref "IC1") (pin "22") (pinfunction "CBUS0_22") (pintype "bidirectional"))
    )
    (net (code "84") (name "unconnected-(IC1-CBUS1-Pad21)") (class "Default")
      (node (ref "IC1") (pin "21") (pinfunction "CBUS1_21") (pintype "bidirectional"))
    )
    (net (code "85") (name "unconnected-(IC1-CBUS2-Pad10)") (class "Default")
      (node (ref "IC1") (pin "10") (pinfunction "CBUS2_10") (pintype "bidirectional"))
    )
    (net (code "86") (name "unconnected-(IC1-CBUS3-Pad11)") (class "Default")
      (node (ref "IC1") (pin "11") (pinfunction "CBUS3_11") (pintype "bidirectional"))
    )
    (net (code "87") (name "unconnected-(IC1-CBUS4-Pad9)") (class "Default")
      (node (ref "IC1") (pin "9") (pinfunction "CBUS4_9") (pintype "bidirectional"))
    )
    (net (code "88") (name "unconnected-(IC1-OSCI-Pad27)") (class "Default")
      (node (ref "IC1") (pin "27") (pinfunction "OSCI_27") (pintype "input"))
    )
    (net (code "89") (name "unconnected-(IC1-OSCO-Pad28)") (class "Default")
      (node (ref "IC1") (pin "28") (pinfunction "OSCO_28") (pintype "output"))
    )
    (net (code "90") (name "unconnected-(IC1-~{CTS}-Pad8)") (class "Default")
      (node (ref "IC1") (pin "8") (pinfunction "~{CTS}_8") (pintype "input"))
    )
    (net (code "91") (name "unconnected-(IC1-~{DCD}-Pad7)") (class "Default")
      (node (ref "IC1") (pin "7") (pinfunction "~{DCD}_7") (pintype "input"))
    )
    (net (code "92") (name "unconnected-(IC1-~{DSR}-Pad6)") (class "Default")
      (node (ref "IC1") (pin "6") (pinfunction "~{DSR}_6") (pintype "input"))
    )
    (net (code "93") (name "unconnected-(IC1-~{RESET}-Pad18)") (class "Default")
      (node (ref "IC1") (pin "18") (pinfunction "~{RESET}_18") (pintype "input"))
    )
    (net (code "94") (name "unconnected-(IC1-~{RI}-Pad3)") (class "Default")
      (node (ref "IC1") (pin "3") (pinfunction "~{RI}_3") (pintype "input"))
    )
    (net (code "95") (name "unconnected-(IC1-~{RTS}-Pad32)") (class "Default")
      (node (ref "IC1") (pin "32") (pinfunction "~{RTS}_32") (pintype "output"))
    )
    (net (code "96") (name "unconnected-(IC2-PA1(ADC1{slash}PCINT1)-Pad36)") (class "Default")
      (node (ref "IC2") (pin "36") (pinfunction "PA1(ADC1/PCINT1)_36") (pintype "bidirectional"))
    )
    (net (code "97") (name "unconnected-(IC2-PA5(ADC5{slash}PCINT5)-Pad32)") (class "Default")
      (node (ref "IC2") (pin "32") (pinfunction "PA5(ADC5/PCINT5)_32") (pintype "bidirectional"))
    )
    (net (code "98") (name "unconnected-(IC2-PA6(ADC6{slash}PCINT6)-Pad31)") (class "Default")
      (node (ref "IC2") (pin "31") (pinfunction "PA6(ADC6/PCINT6)_31") (pintype "bidirectional"))
    )
    (net (code "99") (name "unconnected-(IC2-PA7(ADC7{slash}PCINT7)-Pad30)") (class "Default")
      (node (ref "IC2") (pin "30") (pinfunction "PA7(ADC7/PCINT7)_30") (pintype "bidirectional"))
    )
    (net (code "100") (name "unconnected-(IC2-PB0(PCINT8{slash}XCK0{slash}T0)-Pad40)") (class "Default")
      (node (ref "IC2") (pin "40") (pinfunction "PB0(PCINT8/XCK0/T0)_40") (pintype "bidirectional"))
    )
    (net (code "101") (name "unconnected-(IC2-PB1(PCINT9{slash}CLKO{slash}T1)-Pad41)") (class "Default")
      (node (ref "IC2") (pin "41") (pinfunction "PB1(PCINT9/CLKO/T1)_41") (pintype "bidirectional"))
    )
    (net (code "102") (name "unconnected-(IC2-PC6(TOSC1{slash}PCINT22)-Pad25)") (class "Default")
      (node (ref "IC2") (pin "25") (pinfunction "PC6(TOSC1/PCINT22)_25") (pintype "bidirectional"))
    )
    (net (code "103") (name "unconnected-(IC2-PC7(TOSC2{slash}PCINT23)-Pad26)") (class "Default")
      (node (ref "IC2") (pin "26") (pinfunction "PC7(TOSC2/PCINT23)_26") (pintype "bidirectional"))
    )
    (net (code "104") (name "unconnected-(IC4-DNC-Pad7)") (class "Default")
      (node (ref "IC4") (pin "7") (pinfunction "DNC_7") (pintype "passive"))
    )
    (net (code "105") (name "unconnected-(IC4-DUPLED-Pad26)") (class "Default")
      (node (ref "IC4") (pin "26") (pinfunction "DUPLED_26") (pintype "passive"))
    )
    (net (code "106") (name "unconnected-(IC4-NC-Pad12)") (class "Default")
      (node (ref "IC4") (pin "12") (pinfunction "NC_12") (pintype "passive"))
    )
    (net (code "107") (name "unconnected-(IC4-NC-Pad13)") (class "Default")
      (node (ref "IC4") (pin "13") (pinfunction "NC_13") (pintype "passive"))
    )
    (net (code "108") (name "unconnected-(IC4-NC-Pad46)") (class "Default")
      (node (ref "IC4") (pin "46") (pinfunction "NC_46") (pintype "passive"))
    )
    (net (code "109") (name "unconnected-(IC4-NC-Pad47)") (class "Default")
      (node (ref "IC4") (pin "47") (pinfunction "NC_47") (pintype "passive"))
    )
    (net (code "110") (name "unconnected-(IC4-PMODE0-Pad45)") (class "Default")
      (node (ref "IC4") (pin "45") (pinfunction "PMODE0_45") (pintype "passive"))
    )
    (net (code "111") (name "unconnected-(IC4-PMODE1-Pad44)") (class "Default")
      (node (ref "IC4") (pin "44") (pinfunction "PMODE1_44") (pintype "passive"))
    )
    (net (code "112") (name "unconnected-(IC4-PMODE2-Pad43)") (class "Default")
      (node (ref "IC4") (pin "43") (pinfunction "PMODE2_43") (pintype "passive"))
    )
    (net (code "113") (name "unconnected-(IC4-RSVD-Pad23)") (class "Default")
      (node (ref "IC4") (pin "23") (pinfunction "RSVD_23") (pintype "passive"))
    )
    (net (code "114") (name "unconnected-(IC4-RSVD-Pad38)") (class "Default")
      (node (ref "IC4") (pin "38") (pinfunction "RSVD_38") (pintype "passive"))
    )
    (net (code "115") (name "unconnected-(IC4-RSVD-Pad39)") (class "Default")
      (node (ref "IC4") (pin "39") (pinfunction "RSVD_39") (pintype "passive"))
    )
    (net (code "116") (name "unconnected-(IC4-RSVD-Pad40)") (class "Default")
      (node (ref "IC4") (pin "40") (pinfunction "RSVD_40") (pintype "passive"))
    )
    (net (code "117") (name "unconnected-(IC4-RSVD-Pad41)") (class "Default")
      (node (ref "IC4") (pin "41") (pinfunction "RSVD_41") (pintype "passive"))
    )
    (net (code "118") (name "unconnected-(IC4-RSVD-Pad42)") (class "Default")
      (node (ref "IC4") (pin "42") (pinfunction "RSVD_42") (pintype "passive"))
    )
    (net (code "119") (name "unconnected-(IC4-SPDLED-Pad24)") (class "Default")
      (node (ref "IC4") (pin "24") (pinfunction "SPDLED_24") (pintype "passive"))
    )
    (net (code "120") (name "unconnected-(IC4-VBG-Pad18)") (class "Default")
      (node (ref "IC4") (pin "18") (pinfunction "VBG_18") (pintype "passive"))
    )
    (net (code "121") (name "unconnected-(U$7-ADJ-PadP4)") (class "Default")
      (node (ref "U$7") (pin "P4") (pinfunction "ADJ_P4") (pintype "input"))
    )
    (net (code "122") (name "unconnected-(U2-ID-Pad4)") (class "Default")
      (node (ref "U2") (pin "4") (pinfunction "ID_4") (pintype "bidirectional"))
    )
  )
)
